# esquematico.net
KiCad netlist of a schematic drawn in EAGLE
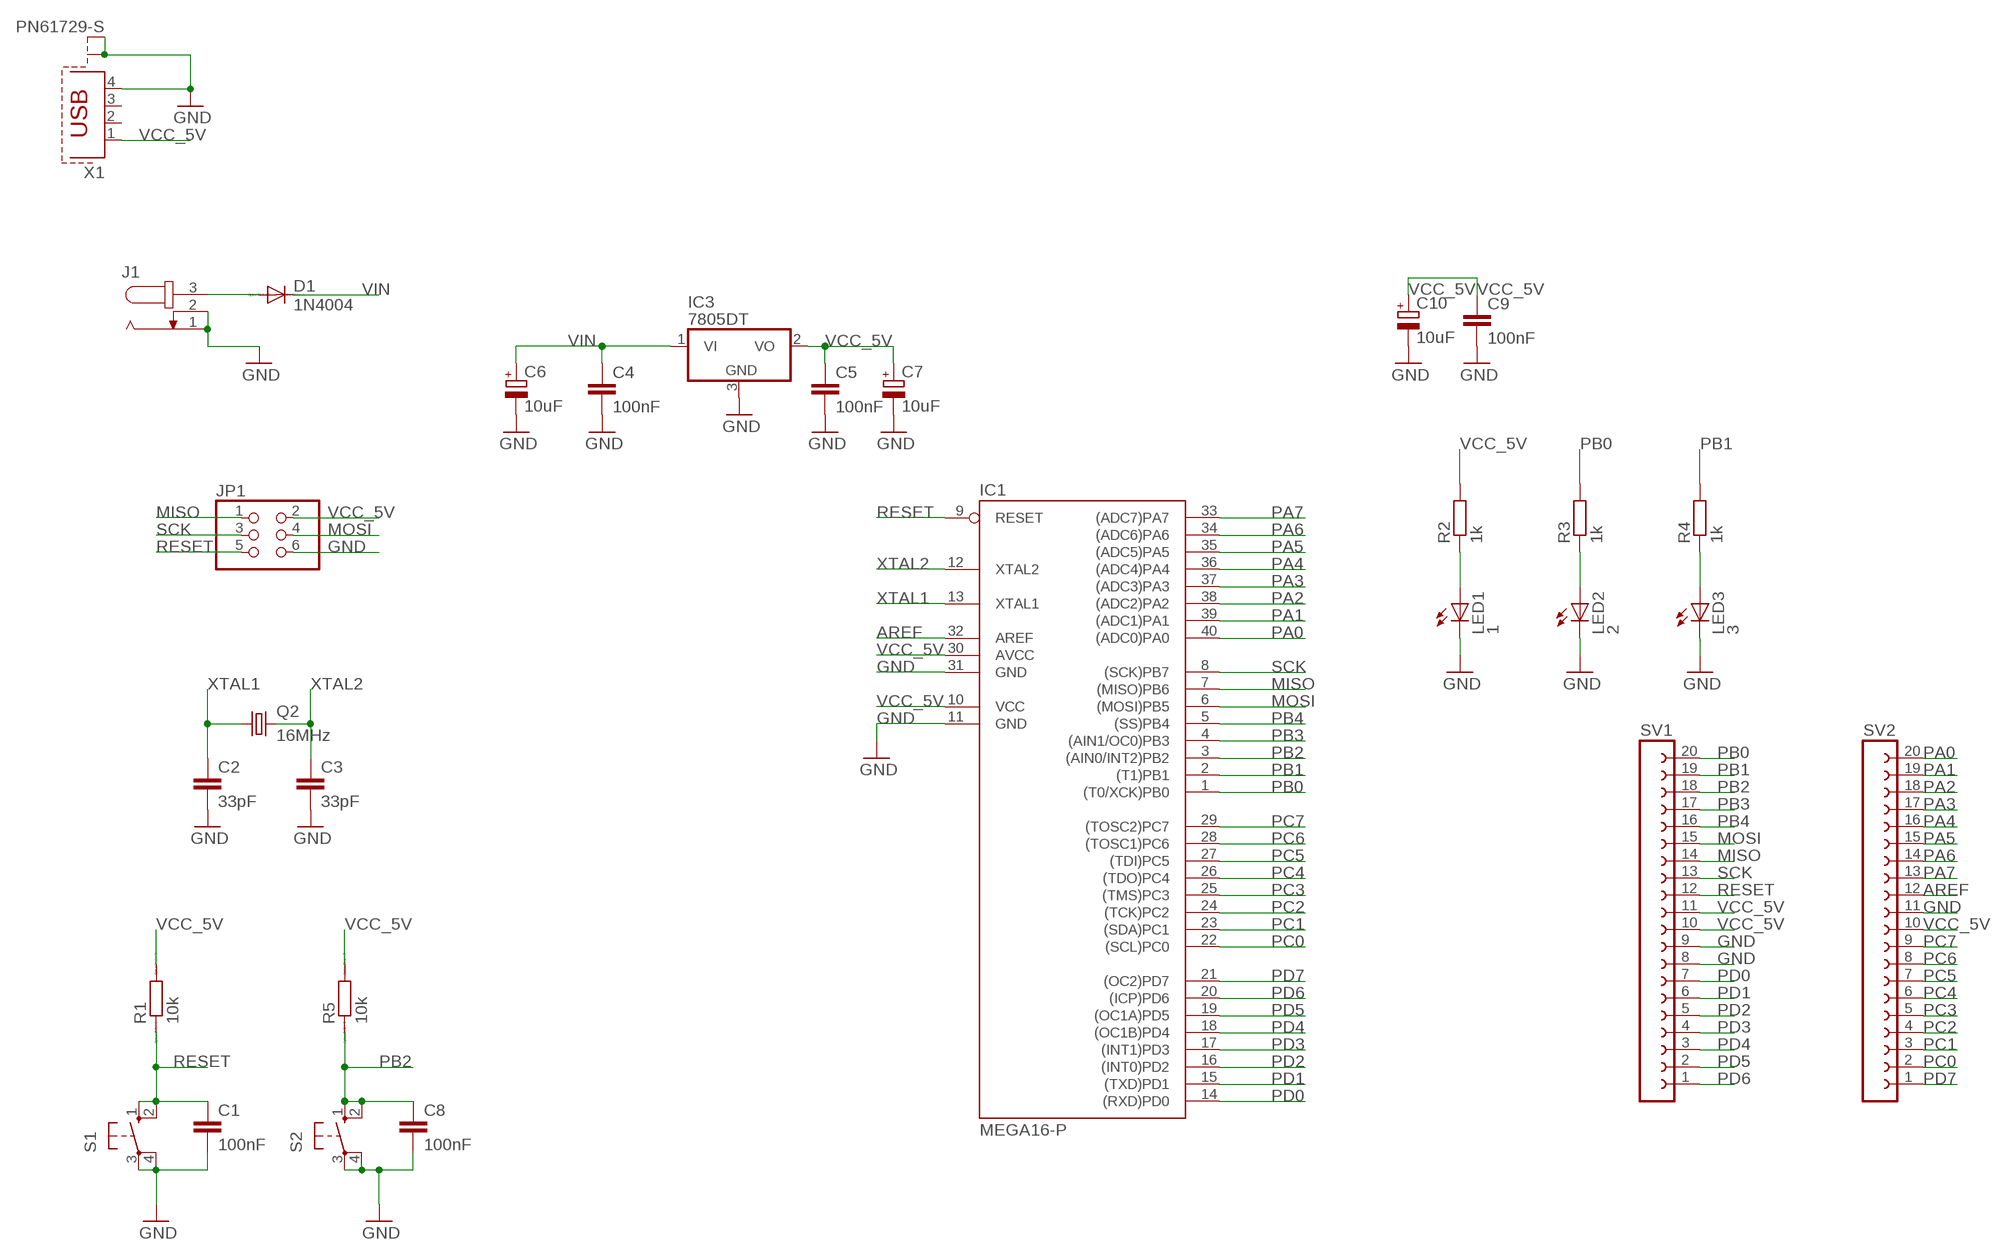
[diagram p0: schematic, sheet 1]

(export (version "E")
  (design (tool "Eeschema 10.0.6"))
  (components
    (comp (ref "C1")
      (value "100nF")
      (footprint "eagle-import:C1206")
      (libsource (lib "eagle-import") (part "C-EUC1206"))
    )
    (comp (ref "C2")
      (value "33pF")
      (footprint "eagle-import:C1206")
      (libsource (lib "eagle-import") (part "resistor_C-EUC1206"))
    )
    (comp (ref "C3")
      (value "33pF")
      (footprint "eagle-import:C1206")
      (libsource (lib "eagle-import") (part "resistor_C-EUC1206"))
    )
    (comp (ref "C4")
      (value "100nF")
      (footprint "eagle-import:C1206")
      (libsource (lib "eagle-import") (part "C-EUC1206"))
    )
    (comp (ref "C5")
      (value "100nF")
      (footprint "eagle-import:C1206")
      (libsource (lib "eagle-import") (part "C-EUC1206"))
    )
    (comp (ref "C6")
      (value "10uF")
      (footprint "eagle-import:E2,5-6E")
      (libsource (lib "eagle-import") (part "CPOL-EUE2,5-6E"))
    )
    (comp (ref "C7")
      (value "10uF")
      (footprint "eagle-import:E2,5-6E")
      (libsource (lib "eagle-import") (part "CPOL-EUE2,5-6E"))
    )
    (comp (ref "C8")
      (value "100nF")
      (footprint "eagle-import:C1206")
      (libsource (lib "eagle-import") (part "C-EUC1206"))
    )
    (comp (ref "C9")
      (value "100nF")
      (footprint "eagle-import:C1206")
      (libsource (lib "eagle-import") (part "C-EUC1206"))
    )
    (comp (ref "C10")
      (value "10uF")
      (footprint "eagle-import:E2,5-6E")
      (libsource (lib "eagle-import") (part "CPOL-EUE2,5-6E"))
    )
    (comp (ref "D1")
      (value "1N4004")
      (footprint "eagle-import:DO41-10")
      (libsource (lib "eagle-import") (part "1N4004"))
    )
    (comp (ref "IC1")
      (value "MEGA16-P")
      (footprint "eagle-import:DIL40")
      (fields (field (name "MPN") "ATMEGA16-16PU"))
      (libsource (lib "eagle-import") (part "MEGA16-P"))
    )
    (comp (ref "IC3")
      (value "7805DT")
      (footprint "eagle-import:TO252")
      (libsource (lib "eagle-import") (part "78DT05"))
    )
    (comp (ref "J1")
      (value "JACK-PLUG1")
      (footprint "eagle-import:SPC4078")
      (libsource (lib "eagle-import") (part "JACK-PLUG1"))
    )
    (comp (ref "JP1")
      (value "PINHD-2X3")
      (footprint "eagle-import:2X03")
      (libsource (lib "eagle-import") (part "PINHD-2X3"))
    )
    (comp (ref "LED1")
      (value "1")
      (footprint "eagle-import:LED3MM")
      (libsource (lib "eagle-import") (part "LED3MM"))
    )
    (comp (ref "LED2")
      (value "2")
      (footprint "eagle-import:LED3MM")
      (libsource (lib "eagle-import") (part "LED3MM"))
    )
    (comp (ref "LED3")
      (value "3")
      (footprint "eagle-import:LED3MM")
      (libsource (lib "eagle-import") (part "LED3MM"))
    )
    (comp (ref "Q2")
      (value "16MHz")
      (footprint "eagle-import:HC49_S")
      (libsource (lib "eagle-import") (part "CRYSTALHC49S"))
    )
    (comp (ref "R1")
      (value "10k")
      (footprint "eagle-import:R1206")
      (libsource (lib "eagle-import") (part "RR1206"))
    )
    (comp (ref "R2")
      (value "1k")
      (footprint "eagle-import:R1206")
      (libsource (lib "eagle-import") (part "R-EU_R1206"))
    )
    (comp (ref "R3")
      (value "1k")
      (footprint "eagle-import:R1206")
      (libsource (lib "eagle-import") (part "R-EU_R1206"))
    )
    (comp (ref "R4")
      (value "1k")
      (footprint "eagle-import:R1206")
      (libsource (lib "eagle-import") (part "R-EU_R1206"))
    )
    (comp (ref "R5")
      (value "10k")
      (footprint "eagle-import:R1206")
      (libsource (lib "eagle-import") (part "RR1206"))
    )
    (comp (ref "S1")
      (value "10-XX")
      (footprint "eagle-import:B3F-10XX")
      (fields (field (name "MPN") "B3F-1000"))
      (libsource (lib "eagle-import") (part "10-XX"))
    )
    (comp (ref "S2")
      (value "10-XX")
      (footprint "eagle-import:B3F-10XX")
      (fields (field (name "MPN") "B3F-1000"))
      (libsource (lib "eagle-import") (part "10-XX"))
    )
    (comp (ref "SV1")
      (value "FE20-1")
      (footprint "eagle-import:FE20")
      (libsource (lib "eagle-import") (part "FE20-1"))
    )
    (comp (ref "SV2")
      (value "FE20-1")
      (footprint "eagle-import:FE20")
      (libsource (lib "eagle-import") (part "FE20-1"))
    )
    (comp (ref "X1")
      (value "PN61729-S")
      (footprint "eagle-import:PN61729-S")
      (libsource (lib "eagle-import") (part "PN61729-S"))
    )
  )
  (nets
    (net (code "1") (name "/AREF") (class "Default")
      (node (ref "IC1") (pin "32") (pinfunction "AREF_32") (pintype "passive"))
      (node (ref "SV2") (pin "12") (pinfunction "12_12") (pintype "passive"))
    )
    (net (code "2") (name "/MISO") (class "Default")
      (node (ref "IC1") (pin "7") (pinfunction "(MISO)PB6_7") (pintype "bidirectional"))
      (node (ref "JP1") (pin "1") (pinfunction "1_1") (pintype "passive"))
      (node (ref "SV1") (pin "14") (pinfunction "14_14") (pintype "passive"))
    )
    (net (code "3") (name "/MOSI") (class "Default")
      (node (ref "IC1") (pin "6") (pinfunction "(MOSI)PB5_6") (pintype "bidirectional"))
      (node (ref "JP1") (pin "4") (pinfunction "4_4") (pintype "passive"))
      (node (ref "SV1") (pin "15") (pinfunction "15_15") (pintype "passive"))
    )
    (net (code "4") (name "/PA0") (class "Default")
      (node (ref "IC1") (pin "40") (pinfunction "(ADC0)PA0_40") (pintype "bidirectional"))
      (node (ref "SV2") (pin "20") (pinfunction "20_20") (pintype "passive"))
    )
    (net (code "5") (name "/PA1") (class "Default")
      (node (ref "IC1") (pin "39") (pinfunction "(ADC1)PA1_39") (pintype "bidirectional"))
      (node (ref "SV2") (pin "19") (pinfunction "19_19") (pintype "passive"))
    )
    (net (code "6") (name "/PA2") (class "Default")
      (node (ref "IC1") (pin "38") (pinfunction "(ADC2)PA2_38") (pintype "bidirectional"))
      (node (ref "SV2") (pin "18") (pinfunction "18_18") (pintype "passive"))
    )
    (net (code "7") (name "/PA3") (class "Default")
      (node (ref "IC1") (pin "37") (pinfunction "(ADC3)PA3_37") (pintype "bidirectional"))
      (node (ref "SV2") (pin "17") (pinfunction "17_17") (pintype "passive"))
    )
    (net (code "8") (name "/PA4") (class "Default")
      (node (ref "IC1") (pin "36") (pinfunction "(ADC4)PA4_36") (pintype "bidirectional"))
      (node (ref "SV2") (pin "16") (pinfunction "16_16") (pintype "passive"))
    )
    (net (code "9") (name "/PA5") (class "Default")
      (node (ref "IC1") (pin "35") (pinfunction "(ADC5)PA5_35") (pintype "bidirectional"))
      (node (ref "SV2") (pin "15") (pinfunction "15_15") (pintype "passive"))
    )
    (net (code "10") (name "/PA6") (class "Default")
      (node (ref "IC1") (pin "34") (pinfunction "(ADC6)PA6_34") (pintype "bidirectional"))
      (node (ref "SV2") (pin "14") (pinfunction "14_14") (pintype "passive"))
    )
    (net (code "11") (name "/PA7") (class "Default")
      (node (ref "IC1") (pin "33") (pinfunction "(ADC7)PA7_33") (pintype "bidirectional"))
      (node (ref "SV2") (pin "13") (pinfunction "13_13") (pintype "passive"))
    )
    (net (code "12") (name "/PB0") (class "Default")
      (node (ref "IC1") (pin "1") (pinfunction "(T0/XCK)PB0_1") (pintype "bidirectional"))
      (node (ref "R3") (pin "2") (pinfunction "2_2") (pintype "passive"))
      (node (ref "SV1") (pin "20") (pinfunction "20_20") (pintype "passive"))
    )
    (net (code "13") (name "/PB1") (class "Default")
      (node (ref "IC1") (pin "2") (pinfunction "(T1)PB1_2") (pintype "bidirectional"))
      (node (ref "R4") (pin "2") (pinfunction "2_2") (pintype "passive"))
      (node (ref "SV1") (pin "19") (pinfunction "19_19") (pintype "passive"))
    )
    (net (code "14") (name "/PB2") (class "Default")
      (node (ref "C8") (pin "1") (pinfunction "1_1") (pintype "passive"))
      (node (ref "IC1") (pin "3") (pinfunction "(AIN0/INT2)PB2_3") (pintype "bidirectional"))
      (node (ref "R5") (pin "1") (pinfunction "1_1") (pintype "passive"))
      (node (ref "S2") (pin "1") (pinfunction "S_1") (pintype "passive"))
      (node (ref "S2") (pin "2") (pinfunction "S1_2") (pintype "passive"))
      (node (ref "SV1") (pin "18") (pinfunction "18_18") (pintype "passive"))
    )
    (net (code "15") (name "/PB3") (class "Default")
      (node (ref "IC1") (pin "4") (pinfunction "(AIN1/OC0)PB3_4") (pintype "bidirectional"))
      (node (ref "SV1") (pin "17") (pinfunction "17_17") (pintype "passive"))
    )
    (net (code "16") (name "/PB4") (class "Default")
      (node (ref "IC1") (pin "5") (pinfunction "(SS)PB4_5") (pintype "bidirectional"))
      (node (ref "SV1") (pin "16") (pinfunction "16_16") (pintype "passive"))
    )
    (net (code "17") (name "/PC0") (class "Default")
      (node (ref "IC1") (pin "22") (pinfunction "(SCL)PC0_22") (pintype "bidirectional"))
      (node (ref "SV2") (pin "2") (pinfunction "2_2") (pintype "passive"))
    )
    (net (code "18") (name "/PC1") (class "Default")
      (node (ref "IC1") (pin "23") (pinfunction "(SDA)PC1_23") (pintype "bidirectional"))
      (node (ref "SV2") (pin "3") (pinfunction "3_3") (pintype "passive"))
    )
    (net (code "19") (name "/PC2") (class "Default")
      (node (ref "IC1") (pin "24") (pinfunction "(TCK)PC2_24") (pintype "bidirectional"))
      (node (ref "SV2") (pin "4") (pinfunction "4_4") (pintype "passive"))
    )
    (net (code "20") (name "/PC3") (class "Default")
      (node (ref "IC1") (pin "25") (pinfunction "(TMS)PC3_25") (pintype "bidirectional"))
      (node (ref "SV2") (pin "5") (pinfunction "5_5") (pintype "passive"))
    )
    (net (code "21") (name "/PC4") (class "Default")
      (node (ref "IC1") (pin "26") (pinfunction "(TDO)PC4_26") (pintype "bidirectional"))
      (node (ref "SV2") (pin "6") (pinfunction "6_6") (pintype "passive"))
    )
    (net (code "22") (name "/PC5") (class "Default")
      (node (ref "IC1") (pin "27") (pinfunction "(TDI)PC5_27") (pintype "bidirectional"))
      (node (ref "SV2") (pin "7") (pinfunction "7_7") (pintype "passive"))
    )
    (net (code "23") (name "/PC6") (class "Default")
      (node (ref "IC1") (pin "28") (pinfunction "(TOSC1)PC6_28") (pintype "bidirectional"))
      (node (ref "SV2") (pin "8") (pinfunction "8_8") (pintype "passive"))
    )
    (net (code "24") (name "/PC7") (class "Default")
      (node (ref "IC1") (pin "29") (pinfunction "(TOSC2)PC7_29") (pintype "bidirectional"))
      (node (ref "SV2") (pin "9") (pinfunction "9_9") (pintype "passive"))
    )
    (net (code "25") (name "/PD0") (class "Default")
      (node (ref "IC1") (pin "14") (pinfunction "(RXD)PD0_14") (pintype "bidirectional"))
      (node (ref "SV1") (pin "7") (pinfunction "7_7") (pintype "passive"))
    )
    (net (code "26") (name "/PD1") (class "Default")
      (node (ref "IC1") (pin "15") (pinfunction "(TXD)PD1_15") (pintype "bidirectional"))
      (node (ref "SV1") (pin "6") (pinfunction "6_6") (pintype "passive"))
    )
    (net (code "27") (name "/PD2") (class "Default")
      (node (ref "IC1") (pin "16") (pinfunction "(INT0)PD2_16") (pintype "bidirectional"))
      (node (ref "SV1") (pin "5") (pinfunction "5_5") (pintype "passive"))
    )
    (net (code "28") (name "/PD3") (class "Default")
      (node (ref "IC1") (pin "17") (pinfunction "(INT1)PD3_17") (pintype "bidirectional"))
      (node (ref "SV1") (pin "4") (pinfunction "4_4") (pintype "passive"))
    )
    (net (code "29") (name "/PD4") (class "Default")
      (node (ref "IC1") (pin "18") (pinfunction "(OC1B)PD4_18") (pintype "bidirectional"))
      (node (ref "SV1") (pin "3") (pinfunction "3_3") (pintype "passive"))
    )
    (net (code "30") (name "/PD5") (class "Default")
      (node (ref "IC1") (pin "19") (pinfunction "(OC1A)PD5_19") (pintype "bidirectional"))
      (node (ref "SV1") (pin "2") (pinfunction "2_2") (pintype "passive"))
    )
    (net (code "31") (name "/PD6") (class "Default")
      (node (ref "IC1") (pin "20") (pinfunction "(ICP)PD6_20") (pintype "bidirectional"))
      (node (ref "SV1") (pin "1") (pinfunction "1_1") (pintype "passive"))
    )
    (net (code "32") (name "/PD7") (class "Default")
      (node (ref "IC1") (pin "21") (pinfunction "(OC2)PD7_21") (pintype "bidirectional"))
      (node (ref "SV2") (pin "1") (pinfunction "1_1") (pintype "passive"))
    )
    (net (code "33") (name "/RESET") (class "Default")
      (node (ref "C1") (pin "1") (pinfunction "1_1") (pintype "passive"))
      (node (ref "IC1") (pin "9") (pinfunction "RESET_9") (pintype "input"))
      (node (ref "JP1") (pin "5") (pinfunction "5_5") (pintype "passive"))
      (node (ref "R1") (pin "1") (pinfunction "1_1") (pintype "passive"))
      (node (ref "S1") (pin "1") (pinfunction "S_1") (pintype "passive"))
      (node (ref "S1") (pin "2") (pinfunction "S1_2") (pintype "passive"))
      (node (ref "SV1") (pin "12") (pinfunction "12_12") (pintype "passive"))
    )
    (net (code "34") (name "/SCK") (class "Default")
      (node (ref "IC1") (pin "8") (pinfunction "(SCK)PB7_8") (pintype "bidirectional"))
      (node (ref "JP1") (pin "3") (pinfunction "3_3") (pintype "passive"))
      (node (ref "SV1") (pin "13") (pinfunction "13_13") (pintype "passive"))
    )
    (net (code "35") (name "/VCC_5V") (class "Default")
      (node (ref "C10") (pin "+") (pinfunction "+_+") (pintype "passive"))
      (node (ref "C5") (pin "1") (pinfunction "1_1") (pintype "passive"))
      (node (ref "C7") (pin "+") (pinfunction "+_+") (pintype "passive"))
      (node (ref "C9") (pin "1") (pinfunction "1_1") (pintype "passive"))
      (node (ref "IC1") (pin "10") (pinfunction "VCC_10") (pintype "power_in"))
      (node (ref "IC1") (pin "30") (pinfunction "AVCC_30") (pintype "power_in"))
      (node (ref "IC3") (pin "2") (pinfunction "VO_2") (pintype "passive"))
      (node (ref "JP1") (pin "2") (pinfunction "2_2") (pintype "passive"))
      (node (ref "R1") (pin "2") (pinfunction "2_2") (pintype "passive"))
      (node (ref "R2") (pin "2") (pinfunction "2_2") (pintype "passive"))
      (node (ref "R5") (pin "2") (pinfunction "2_2") (pintype "passive"))
      (node (ref "SV1") (pin "10") (pinfunction "10_10") (pintype "passive"))
      (node (ref "SV1") (pin "11") (pinfunction "11_11") (pintype "passive"))
      (node (ref "SV2") (pin "10") (pinfunction "10_10") (pintype "passive"))
      (node (ref "X1") (pin "1") (pinfunction "1_1") (pintype "passive"))
    )
    (net (code "36") (name "/VIN") (class "Default")
      (node (ref "C4") (pin "1") (pinfunction "1_1") (pintype "passive"))
      (node (ref "C6") (pin "+") (pinfunction "+_+") (pintype "passive"))
      (node (ref "D1") (pin "C") (pinfunction "C_C") (pintype "passive"))
      (node (ref "IC3") (pin "1") (pinfunction "VI_1") (pintype "input"))
    )
    (net (code "37") (name "/XTAL1") (class "Default")
      (node (ref "C2") (pin "1") (pinfunction "1_1") (pintype "passive"))
      (node (ref "IC1") (pin "13") (pinfunction "XTAL1_13") (pintype "bidirectional"))
      (node (ref "Q2") (pin "1") (pinfunction "1_1") (pintype "passive"))
    )
    (net (code "38") (name "/XTAL2") (class "Default")
      (node (ref "C3") (pin "1") (pinfunction "1_1") (pintype "passive"))
      (node (ref "IC1") (pin "12") (pinfunction "XTAL2_12") (pintype "bidirectional"))
      (node (ref "Q2") (pin "2") (pinfunction "2_2") (pintype "passive"))
    )
    (net (code "39") (name "GND") (class "Default")
      (node (ref "C1") (pin "2") (pinfunction "2_2") (pintype "passive"))
      (node (ref "C10") (pin "-") (pinfunction "-_-") (pintype "passive"))
      (node (ref "C2") (pin "2") (pinfunction "2_2") (pintype "passive"))
      (node (ref "C3") (pin "2") (pinfunction "2_2") (pintype "passive"))
      (node (ref "C4") (pin "2") (pinfunction "2_2") (pintype "passive"))
      (node (ref "C5") (pin "2") (pinfunction "2_2") (pintype "passive"))
      (node (ref "C6") (pin "-") (pinfunction "-_-") (pintype "passive"))
      (node (ref "C7") (pin "-") (pinfunction "-_-") (pintype "passive"))
      (node (ref "C8") (pin "2") (pinfunction "2_2") (pintype "passive"))
      (node (ref "C9") (pin "2") (pinfunction "2_2") (pintype "passive"))
      (node (ref "IC1") (pin "11") (pinfunction "GND_11") (pintype "power_in"))
      (node (ref "IC1") (pin "31") (pinfunction "GND_31") (pintype "power_in"))
      (node (ref "IC3") (pin "3") (pinfunction "GND_3") (pintype "passive"))
      (node (ref "J1") (pin "1") (pinfunction "1_1") (pintype "passive"))
      (node (ref "J1") (pin "2") (pinfunction "2_2") (pintype "passive"))
      (node (ref "JP1") (pin "6") (pinfunction "6_6") (pintype "passive"))
      (node (ref "LED1") (pin "K") (pinfunction "C_K") (pintype "passive"))
      (node (ref "LED2") (pin "K") (pinfunction "C_K") (pintype "passive"))
      (node (ref "LED3") (pin "K") (pinfunction "C_K") (pintype "passive"))
      (node (ref "S1") (pin "3") (pinfunction "P_3") (pintype "passive"))
      (node (ref "S1") (pin "4") (pinfunction "P1_4") (pintype "passive"))
      (node (ref "S2") (pin "3") (pinfunction "P_3") (pintype "passive"))
      (node (ref "S2") (pin "4") (pinfunction "P1_4") (pintype "passive"))
      (node (ref "SV1") (pin "8") (pinfunction "8_8") (pintype "passive"))
      (node (ref "SV1") (pin "9") (pinfunction "9_9") (pintype "passive"))
      (node (ref "SV2") (pin "11") (pinfunction "11_11") (pintype "passive"))
      (node (ref "X1") (pin "4") (pinfunction "4_4") (pintype "passive"))
      (node (ref "X1") (pin "S1") (pinfunction "S1_S1") (pintype "passive"))
      (node (ref "X1") (pin "S2") (pinfunction "S2_S2") (pintype "passive"))
    )
    (net (code "40") (name "Net-(D1-PadA)") (class "Default")
      (node (ref "D1") (pin "A") (pinfunction "A_A") (pintype "passive"))
      (node (ref "J1") (pin "3") (pinfunction "3_3") (pintype "passive"))
    )
    (net (code "41") (name "Net-(LED1-PadA)") (class "Default")
      (node (ref "LED1") (pin "A") (pinfunction "A_A") (pintype "passive"))
      (node (ref "R2") (pin "1") (pinfunction "1_1") (pintype "passive"))
    )
    (net (code "42") (name "Net-(LED2-PadA)") (class "Default")
      (node (ref "LED2") (pin "A") (pinfunction "A_A") (pintype "passive"))
      (node (ref "R3") (pin "1") (pinfunction "1_1") (pintype "passive"))
    )
    (net (code "43") (name "Net-(LED3-PadA)") (class "Default")
      (node (ref "LED3") (pin "A") (pinfunction "A_A") (pintype "passive"))
      (node (ref "R4") (pin "1") (pinfunction "1_1") (pintype "passive"))
    )
    (net (code "44") (name "unconnected-(X1-Pad2)") (class "Default")
      (node (ref "X1") (pin "2") (pinfunction "2_2") (pintype "passive"))
    )
    (net (code "45") (name "unconnected-(X1-Pad3)") (class "Default")
      (node (ref "X1") (pin "3") (pinfunction "3_3") (pintype "passive"))
    )
  )
)
